# WS2812MATRIX.net
KiCad netlist of a schematic drawn in EAGLE
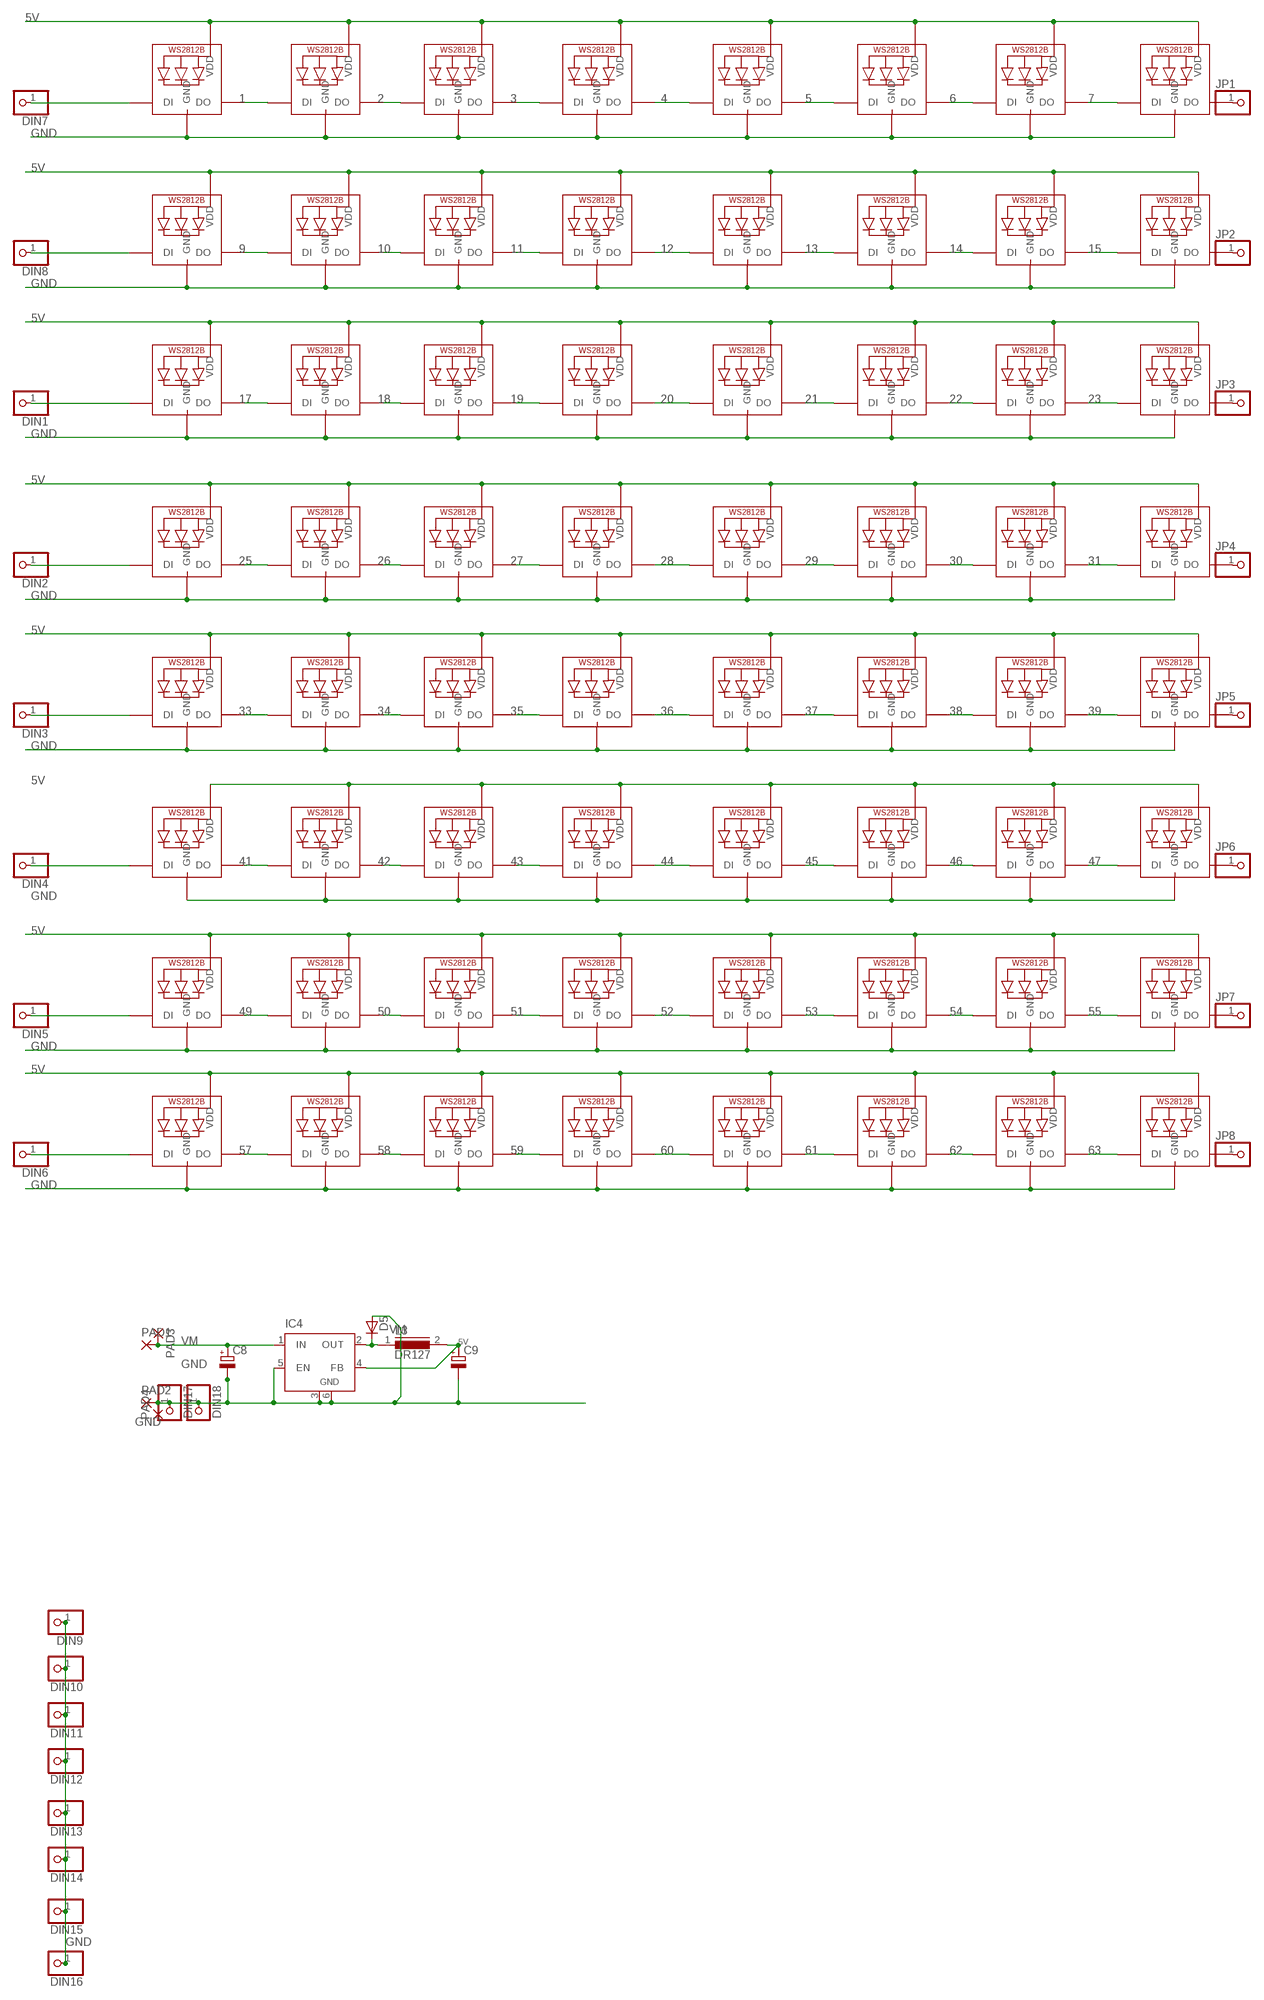
[diagram p0: schematic, sheet 1]

(export (version "E")
  (design (tool "Eeschema 10.0.6"))
  (components
    (comp (ref "C8")
      (value "CPOL-EUE3.5-10")
      (footprint "eagle-import:E3,5-10")
      (libsource (lib "eagle-import") (part "CPOL-EUE3.5-10"))
    )
    (comp (ref "C9")
      (value "CPOL-EUE3.5-10")
      (footprint "eagle-import:E3,5-10")
      (libsource (lib "eagle-import") (part "CPOL-EUE3.5-10"))
    )
    (comp (ref "D5")
      (value "D-SOD-87")
      (footprint "eagle-import:SOD87")
      (libsource (lib "eagle-import") (part "D-SOD-87"))
    )
    (comp (ref "DIN1")
      (value "PINHD-1X1")
      (footprint "eagle-import:1X01")
      (libsource (lib "eagle-import") (part "PINHD-1X1"))
    )
    (comp (ref "DIN2")
      (value "PINHD-1X1")
      (footprint "eagle-import:1X01")
      (libsource (lib "eagle-import") (part "PINHD-1X1"))
    )
    (comp (ref "DIN3")
      (value "PINHD-1X1")
      (footprint "eagle-import:1X01")
      (libsource (lib "eagle-import") (part "PINHD-1X1"))
    )
    (comp (ref "DIN4")
      (value "PINHD-1X1")
      (footprint "eagle-import:1X01")
      (libsource (lib "eagle-import") (part "PINHD-1X1"))
    )
    (comp (ref "DIN5")
      (value "PINHD-1X1")
      (footprint "eagle-import:1X01")
      (libsource (lib "eagle-import") (part "PINHD-1X1"))
    )
    (comp (ref "DIN6")
      (value "PINHD-1X1")
      (footprint "eagle-import:1X01")
      (libsource (lib "eagle-import") (part "PINHD-1X1"))
    )
    (comp (ref "DIN7")
      (value "PINHD-1X1")
      (footprint "eagle-import:1X01")
      (libsource (lib "eagle-import") (part "PINHD-1X1"))
    )
    (comp (ref "DIN8")
      (value "PINHD-1X1")
      (footprint "eagle-import:1X01")
      (libsource (lib "eagle-import") (part "PINHD-1X1"))
    )
    (comp (ref "DIN9")
      (value "PINHD-1X1")
      (footprint "eagle-import:1X01")
      (libsource (lib "eagle-import") (part "PINHD-1X1"))
    )
    (comp (ref "DIN10")
      (value "PINHD-1X1")
      (footprint "eagle-import:1X01")
      (libsource (lib "eagle-import") (part "PINHD-1X1"))
    )
    (comp (ref "DIN11")
      (value "PINHD-1X1")
      (footprint "eagle-import:1X01")
      (libsource (lib "eagle-import") (part "PINHD-1X1"))
    )
    (comp (ref "DIN12")
      (value "PINHD-1X1")
      (footprint "eagle-import:1X01")
      (libsource (lib "eagle-import") (part "PINHD-1X1"))
    )
    (comp (ref "DIN13")
      (value "PINHD-1X1")
      (footprint "eagle-import:1X01")
      (libsource (lib "eagle-import") (part "PINHD-1X1"))
    )
    (comp (ref "DIN14")
      (value "PINHD-1X1")
      (footprint "eagle-import:1X01")
      (libsource (lib "eagle-import") (part "PINHD-1X1"))
    )
    (comp (ref "DIN15")
      (value "PINHD-1X1")
      (footprint "eagle-import:1X01")
      (libsource (lib "eagle-import") (part "PINHD-1X1"))
    )
    (comp (ref "DIN16")
      (value "PINHD-1X1")
      (footprint "eagle-import:1X01")
      (libsource (lib "eagle-import") (part "PINHD-1X1"))
    )
    (comp (ref "DIN17")
      (value "PINHD-1X1")
      (footprint "eagle-import:1X01")
      (libsource (lib "eagle-import") (part "PINHD-1X1"))
    )
    (comp (ref "DIN18")
      (value "PINHD-1X1")
      (footprint "eagle-import:1X01")
      (libsource (lib "eagle-import") (part "PINHD-1X1"))
    )
    (comp (ref "IC4")
      (value "LM2596S")
      (footprint "eagle-import:TO263-5")
      (libsource (lib "eagle-import") (part "LM2596S"))
    )
    (comp (ref "JP1")
      (value "PINHD-1X1")
      (footprint "eagle-import:1X01")
      (libsource (lib "eagle-import") (part "PINHD-1X1"))
    )
    (comp (ref "JP2")
      (value "PINHD-1X1")
      (footprint "eagle-import:1X01")
      (libsource (lib "eagle-import") (part "PINHD-1X1"))
    )
    (comp (ref "JP3")
      (value "PINHD-1X1")
      (footprint "eagle-import:1X01")
      (libsource (lib "eagle-import") (part "PINHD-1X1"))
    )
    (comp (ref "JP4")
      (value "PINHD-1X1")
      (footprint "eagle-import:1X01")
      (libsource (lib "eagle-import") (part "PINHD-1X1"))
    )
    (comp (ref "JP5")
      (value "PINHD-1X1")
      (footprint "eagle-import:1X01")
      (libsource (lib "eagle-import") (part "PINHD-1X1"))
    )
    (comp (ref "JP6")
      (value "PINHD-1X1")
      (footprint "eagle-import:1X01")
      (libsource (lib "eagle-import") (part "PINHD-1X1"))
    )
    (comp (ref "JP7")
      (value "PINHD-1X1")
      (footprint "eagle-import:1X01")
      (libsource (lib "eagle-import") (part "PINHD-1X1"))
    )
    (comp (ref "JP8")
      (value "PINHD-1X1")
      (footprint "eagle-import:1X01")
      (libsource (lib "eagle-import") (part "PINHD-1X1"))
    )
    (comp (ref "L3")
      (value "DR127")
      (footprint "eagle-import:DR127")
      (libsource (lib "eagle-import") (part "DR127"))
    )
    (comp (ref "LED1")
      (value "WS2812B5050")
      (footprint "eagle-import:WS2812B")
      (libsource (lib "eagle-import") (part "WS2812B5050"))
    )
    (comp (ref "LED2")
      (value "WS2812B5050")
      (footprint "eagle-import:WS2812B")
      (libsource (lib "eagle-import") (part "WS2812B5050"))
    )
    (comp (ref "LED3")
      (value "WS2812B5050")
      (footprint "eagle-import:WS2812B")
      (libsource (lib "eagle-import") (part "WS2812B5050"))
    )
    (comp (ref "LED4")
      (value "WS2812B5050")
      (footprint "eagle-import:WS2812B")
      (libsource (lib "eagle-import") (part "WS2812B5050"))
    )
    (comp (ref "LED5")
      (value "WS2812B5050")
      (footprint "eagle-import:WS2812B")
      (libsource (lib "eagle-import") (part "WS2812B5050"))
    )
    (comp (ref "LED6")
      (value "WS2812B5050")
      (footprint "eagle-import:WS2812B")
      (libsource (lib "eagle-import") (part "WS2812B5050"))
    )
    (comp (ref "LED7")
      (value "WS2812B5050")
      (footprint "eagle-import:WS2812B")
      (libsource (lib "eagle-import") (part "WS2812B5050"))
    )
    (comp (ref "LED8")
      (value "WS2812B5050")
      (footprint "eagle-import:WS2812B")
      (libsource (lib "eagle-import") (part "WS2812B5050"))
    )
    (comp (ref "LED9")
      (value "WS2812B5050")
      (footprint "eagle-import:WS2812B")
      (libsource (lib "eagle-import") (part "WS2812B5050"))
    )
    (comp (ref "LED10")
      (value "WS2812B5050")
      (footprint "eagle-import:WS2812B")
      (libsource (lib "eagle-import") (part "WS2812B5050"))
    )
    (comp (ref "LED11")
      (value "WS2812B5050")
      (footprint "eagle-import:WS2812B")
      (libsource (lib "eagle-import") (part "WS2812B5050"))
    )
    (comp (ref "LED12")
      (value "WS2812B5050")
      (footprint "eagle-import:WS2812B")
      (libsource (lib "eagle-import") (part "WS2812B5050"))
    )
    (comp (ref "LED13")
      (value "WS2812B5050")
      (footprint "eagle-import:WS2812B")
      (libsource (lib "eagle-import") (part "WS2812B5050"))
    )
    (comp (ref "LED14")
      (value "WS2812B5050")
      (footprint "eagle-import:WS2812B")
      (libsource (lib "eagle-import") (part "WS2812B5050"))
    )
    (comp (ref "LED15")
      (value "WS2812B5050")
      (footprint "eagle-import:WS2812B")
      (libsource (lib "eagle-import") (part "WS2812B5050"))
    )
    (comp (ref "LED16")
      (value "WS2812B5050")
      (footprint "eagle-import:WS2812B")
      (libsource (lib "eagle-import") (part "WS2812B5050"))
    )
    (comp (ref "LED17")
      (value "WS2812B5050")
      (footprint "eagle-import:WS2812B")
      (libsource (lib "eagle-import") (part "WS2812B5050"))
    )
    (comp (ref "LED18")
      (value "WS2812B5050")
      (footprint "eagle-import:WS2812B")
      (libsource (lib "eagle-import") (part "WS2812B5050"))
    )
    (comp (ref "LED19")
      (value "WS2812B5050")
      (footprint "eagle-import:WS2812B")
      (libsource (lib "eagle-import") (part "WS2812B5050"))
    )
    (comp (ref "LED20")
      (value "WS2812B5050")
      (footprint "eagle-import:WS2812B")
      (libsource (lib "eagle-import") (part "WS2812B5050"))
    )
    (comp (ref "LED21")
      (value "WS2812B5050")
      (footprint "eagle-import:WS2812B")
      (libsource (lib "eagle-import") (part "WS2812B5050"))
    )
    (comp (ref "LED22")
      (value "WS2812B5050")
      (footprint "eagle-import:WS2812B")
      (libsource (lib "eagle-import") (part "WS2812B5050"))
    )
    (comp (ref "LED23")
      (value "WS2812B5050")
      (footprint "eagle-import:WS2812B")
      (libsource (lib "eagle-import") (part "WS2812B5050"))
    )
    (comp (ref "LED24")
      (value "WS2812B5050")
      (footprint "eagle-import:WS2812B")
      (libsource (lib "eagle-import") (part "WS2812B5050"))
    )
    (comp (ref "LED25")
      (value "WS2812B5050")
      (footprint "eagle-import:WS2812B")
      (libsource (lib "eagle-import") (part "WS2812B5050"))
    )
    (comp (ref "LED26")
      (value "WS2812B5050")
      (footprint "eagle-import:WS2812B")
      (libsource (lib "eagle-import") (part "WS2812B5050"))
    )
    (comp (ref "LED27")
      (value "WS2812B5050")
      (footprint "eagle-import:WS2812B")
      (libsource (lib "eagle-import") (part "WS2812B5050"))
    )
    (comp (ref "LED28")
      (value "WS2812B5050")
      (footprint "eagle-import:WS2812B")
      (libsource (lib "eagle-import") (part "WS2812B5050"))
    )
    (comp (ref "LED29")
      (value "WS2812B5050")
      (footprint "eagle-import:WS2812B")
      (libsource (lib "eagle-import") (part "WS2812B5050"))
    )
    (comp (ref "LED30")
      (value "WS2812B5050")
      (footprint "eagle-import:WS2812B")
      (libsource (lib "eagle-import") (part "WS2812B5050"))
    )
    (comp (ref "LED31")
      (value "WS2812B5050")
      (footprint "eagle-import:WS2812B")
      (libsource (lib "eagle-import") (part "WS2812B5050"))
    )
    (comp (ref "LED32")
      (value "WS2812B5050")
      (footprint "eagle-import:WS2812B")
      (libsource (lib "eagle-import") (part "WS2812B5050"))
    )
    (comp (ref "LED33")
      (value "WS2812B5050")
      (footprint "eagle-import:WS2812B")
      (libsource (lib "eagle-import") (part "WS2812B5050"))
    )
    (comp (ref "LED34")
      (value "WS2812B5050")
      (footprint "eagle-import:WS2812B")
      (libsource (lib "eagle-import") (part "WS2812B5050"))
    )
    (comp (ref "LED35")
      (value "WS2812B5050")
      (footprint "eagle-import:WS2812B")
      (libsource (lib "eagle-import") (part "WS2812B5050"))
    )
    (comp (ref "LED36")
      (value "WS2812B5050")
      (footprint "eagle-import:WS2812B")
      (libsource (lib "eagle-import") (part "WS2812B5050"))
    )
    (comp (ref "LED37")
      (value "WS2812B5050")
      (footprint "eagle-import:WS2812B")
      (libsource (lib "eagle-import") (part "WS2812B5050"))
    )
    (comp (ref "LED38")
      (value "WS2812B5050")
      (footprint "eagle-import:WS2812B")
      (libsource (lib "eagle-import") (part "WS2812B5050"))
    )
    (comp (ref "LED39")
      (value "WS2812B5050")
      (footprint "eagle-import:WS2812B")
      (libsource (lib "eagle-import") (part "WS2812B5050"))
    )
    (comp (ref "LED40")
      (value "WS2812B5050")
      (footprint "eagle-import:WS2812B")
      (libsource (lib "eagle-import") (part "WS2812B5050"))
    )
    (comp (ref "LED41")
      (value "WS2812B5050")
      (footprint "eagle-import:WS2812B")
      (libsource (lib "eagle-import") (part "WS2812B5050"))
    )
    (comp (ref "LED42")
      (value "WS2812B5050")
      (footprint "eagle-import:WS2812B")
      (libsource (lib "eagle-import") (part "WS2812B5050"))
    )
    (comp (ref "LED43")
      (value "WS2812B5050")
      (footprint "eagle-import:WS2812B")
      (libsource (lib "eagle-import") (part "WS2812B5050"))
    )
    (comp (ref "LED44")
      (value "WS2812B5050")
      (footprint "eagle-import:WS2812B")
      (libsource (lib "eagle-import") (part "WS2812B5050"))
    )
    (comp (ref "LED45")
      (value "WS2812B5050")
      (footprint "eagle-import:WS2812B")
      (libsource (lib "eagle-import") (part "WS2812B5050"))
    )
    (comp (ref "LED46")
      (value "WS2812B5050")
      (footprint "eagle-import:WS2812B")
      (libsource (lib "eagle-import") (part "WS2812B5050"))
    )
    (comp (ref "LED47")
      (value "WS2812B5050")
      (footprint "eagle-import:WS2812B")
      (libsource (lib "eagle-import") (part "WS2812B5050"))
    )
    (comp (ref "LED48")
      (value "WS2812B5050")
      (footprint "eagle-import:WS2812B")
      (libsource (lib "eagle-import") (part "WS2812B5050"))
    )
    (comp (ref "LED49")
      (value "WS2812B5050")
      (footprint "eagle-import:WS2812B")
      (libsource (lib "eagle-import") (part "WS2812B5050"))
    )
    (comp (ref "LED50")
      (value "WS2812B5050")
      (footprint "eagle-import:WS2812B")
      (libsource (lib "eagle-import") (part "WS2812B5050"))
    )
    (comp (ref "LED51")
      (value "WS2812B5050")
      (footprint "eagle-import:WS2812B")
      (libsource (lib "eagle-import") (part "WS2812B5050"))
    )
    (comp (ref "LED52")
      (value "WS2812B5050")
      (footprint "eagle-import:WS2812B")
      (libsource (lib "eagle-import") (part "WS2812B5050"))
    )
    (comp (ref "LED53")
      (value "WS2812B5050")
      (footprint "eagle-import:WS2812B")
      (libsource (lib "eagle-import") (part "WS2812B5050"))
    )
    (comp (ref "LED54")
      (value "WS2812B5050")
      (footprint "eagle-import:WS2812B")
      (libsource (lib "eagle-import") (part "WS2812B5050"))
    )
    (comp (ref "LED55")
      (value "WS2812B5050")
      (footprint "eagle-import:WS2812B")
      (libsource (lib "eagle-import") (part "WS2812B5050"))
    )
    (comp (ref "LED56")
      (value "WS2812B5050")
      (footprint "eagle-import:WS2812B")
      (libsource (lib "eagle-import") (part "WS2812B5050"))
    )
    (comp (ref "LED57")
      (value "WS2812B5050")
      (footprint "eagle-import:WS2812B")
      (libsource (lib "eagle-import") (part "WS2812B5050"))
    )
    (comp (ref "LED58")
      (value "WS2812B5050")
      (footprint "eagle-import:WS2812B")
      (libsource (lib "eagle-import") (part "WS2812B5050"))
    )
    (comp (ref "LED59")
      (value "WS2812B5050")
      (footprint "eagle-import:WS2812B")
      (libsource (lib "eagle-import") (part "WS2812B5050"))
    )
    (comp (ref "LED60")
      (value "WS2812B5050")
      (footprint "eagle-import:WS2812B")
      (libsource (lib "eagle-import") (part "WS2812B5050"))
    )
    (comp (ref "LED61")
      (value "WS2812B5050")
      (footprint "eagle-import:WS2812B")
      (libsource (lib "eagle-import") (part "WS2812B5050"))
    )
    (comp (ref "LED62")
      (value "WS2812B5050")
      (footprint "eagle-import:WS2812B")
      (libsource (lib "eagle-import") (part "WS2812B5050"))
    )
    (comp (ref "LED63")
      (value "WS2812B5050")
      (footprint "eagle-import:WS2812B")
      (libsource (lib "eagle-import") (part "WS2812B5050"))
    )
    (comp (ref "LED64")
      (value "WS2812B5050")
      (footprint "eagle-import:WS2812B")
      (libsource (lib "eagle-import") (part "WS2812B5050"))
    )
    (comp (ref "PAD1")
      (value "2,54/1,1")
      (footprint "eagle-import:2,54_1,1")
      (libsource (lib "eagle-import") (part "2,54/1,1"))
    )
    (comp (ref "PAD2")
      (value "2,54/1,1")
      (footprint "eagle-import:2,54_1,1")
      (libsource (lib "eagle-import") (part "2,54/1,1"))
    )
    (comp (ref "PAD3")
      (value "2,54/1,1")
      (footprint "eagle-import:2,54_1,1")
      (libsource (lib "eagle-import") (part "2,54/1,1"))
    )
    (comp (ref "PAD4")
      (value "2,54/1,1")
      (footprint "eagle-import:2,54_1,1")
      (libsource (lib "eagle-import") (part "2,54/1,1"))
    )
  )
  (nets
    (net (code "1") (name "/1") (class "Default")
      (node (ref "LED10") (pin "4-DIN") (pinfunction "DI_4-DIN") (pintype "input"))
      (node (ref "LED9") (pin "2-DOUT") (pinfunction "DO_2-DOUT") (pintype "output"))
    )
    (net (code "2") (name "/2") (class "Default")
      (node (ref "LED10") (pin "2-DOUT") (pinfunction "DO_2-DOUT") (pintype "output"))
      (node (ref "LED11") (pin "4-DIN") (pinfunction "DI_4-DIN") (pintype "input"))
    )
    (net (code "3") (name "/3") (class "Default")
      (node (ref "LED11") (pin "2-DOUT") (pinfunction "DO_2-DOUT") (pintype "output"))
      (node (ref "LED12") (pin "4-DIN") (pinfunction "DI_4-DIN") (pintype "input"))
    )
    (net (code "4") (name "/4") (class "Default")
      (node (ref "LED12") (pin "2-DOUT") (pinfunction "DO_2-DOUT") (pintype "output"))
      (node (ref "LED13") (pin "4-DIN") (pinfunction "DI_4-DIN") (pintype "input"))
    )
    (net (code "5") (name "/5") (class "Default")
      (node (ref "LED13") (pin "2-DOUT") (pinfunction "DO_2-DOUT") (pintype "output"))
      (node (ref "LED14") (pin "4-DIN") (pinfunction "DI_4-DIN") (pintype "input"))
    )
    (net (code "6") (name "/5V") (class "Default")
      (node (ref "C9") (pin "+") (pinfunction "+_+") (pintype "passive"))
      (node (ref "IC4") (pin "4") (pinfunction "FB_4") (pintype "input"))
      (node (ref "L3") (pin "2") (pinfunction "2_2") (pintype "passive"))
      (node (ref "LED1") (pin "1-VDD") (pinfunction "VDD_1-VDD") (pintype "power_in"))
      (node (ref "LED10") (pin "1-VDD") (pinfunction "VDD_1-VDD") (pintype "power_in"))
      (node (ref "LED11") (pin "1-VDD") (pinfunction "VDD_1-VDD") (pintype "power_in"))
      (node (ref "LED12") (pin "1-VDD") (pinfunction "VDD_1-VDD") (pintype "power_in"))
      (node (ref "LED13") (pin "1-VDD") (pinfunction "VDD_1-VDD") (pintype "power_in"))
      (node (ref "LED14") (pin "1-VDD") (pinfunction "VDD_1-VDD") (pintype "power_in"))
      (node (ref "LED15") (pin "1-VDD") (pinfunction "VDD_1-VDD") (pintype "power_in"))
      (node (ref "LED16") (pin "1-VDD") (pinfunction "VDD_1-VDD") (pintype "power_in"))
      (node (ref "LED17") (pin "1-VDD") (pinfunction "VDD_1-VDD") (pintype "power_in"))
      (node (ref "LED18") (pin "1-VDD") (pinfunction "VDD_1-VDD") (pintype "power_in"))
      (node (ref "LED19") (pin "1-VDD") (pinfunction "VDD_1-VDD") (pintype "power_in"))
      (node (ref "LED2") (pin "1-VDD") (pinfunction "VDD_1-VDD") (pintype "power_in"))
      (node (ref "LED20") (pin "1-VDD") (pinfunction "VDD_1-VDD") (pintype "power_in"))
      (node (ref "LED21") (pin "1-VDD") (pinfunction "VDD_1-VDD") (pintype "power_in"))
      (node (ref "LED22") (pin "1-VDD") (pinfunction "VDD_1-VDD") (pintype "power_in"))
      (node (ref "LED23") (pin "1-VDD") (pinfunction "VDD_1-VDD") (pintype "power_in"))
      (node (ref "LED24") (pin "1-VDD") (pinfunction "VDD_1-VDD") (pintype "power_in"))
      (node (ref "LED25") (pin "1-VDD") (pinfunction "VDD_1-VDD") (pintype "power_in"))
      (node (ref "LED26") (pin "1-VDD") (pinfunction "VDD_1-VDD") (pintype "power_in"))
      (node (ref "LED27") (pin "1-VDD") (pinfunction "VDD_1-VDD") (pintype "power_in"))
      (node (ref "LED28") (pin "1-VDD") (pinfunction "VDD_1-VDD") (pintype "power_in"))
      (node (ref "LED29") (pin "1-VDD") (pinfunction "VDD_1-VDD") (pintype "power_in"))
      (node (ref "LED3") (pin "1-VDD") (pinfunction "VDD_1-VDD") (pintype "power_in"))
      (node (ref "LED30") (pin "1-VDD") (pinfunction "VDD_1-VDD") (pintype "power_in"))
      (node (ref "LED31") (pin "1-VDD") (pinfunction "VDD_1-VDD") (pintype "power_in"))
      (node (ref "LED32") (pin "1-VDD") (pinfunction "VDD_1-VDD") (pintype "power_in"))
      (node (ref "LED33") (pin "1-VDD") (pinfunction "VDD_1-VDD") (pintype "power_in"))
      (node (ref "LED34") (pin "1-VDD") (pinfunction "VDD_1-VDD") (pintype "power_in"))
      (node (ref "LED35") (pin "1-VDD") (pinfunction "VDD_1-VDD") (pintype "power_in"))
      (node (ref "LED36") (pin "1-VDD") (pinfunction "VDD_1-VDD") (pintype "power_in"))
      (node (ref "LED37") (pin "1-VDD") (pinfunction "VDD_1-VDD") (pintype "power_in"))
      (node (ref "LED38") (pin "1-VDD") (pinfunction "VDD_1-VDD") (pintype "power_in"))
      (node (ref "LED39") (pin "1-VDD") (pinfunction "VDD_1-VDD") (pintype "power_in"))
      (node (ref "LED4") (pin "1-VDD") (pinfunction "VDD_1-VDD") (pintype "power_in"))
      (node (ref "LED40") (pin "1-VDD") (pinfunction "VDD_1-VDD") (pintype "power_in"))
      (node (ref "LED41") (pin "1-VDD") (pinfunction "VDD_1-VDD") (pintype "power_in"))
      (node (ref "LED42") (pin "1-VDD") (pinfunction "VDD_1-VDD") (pintype "power_in"))
      (node (ref "LED43") (pin "1-VDD") (pinfunction "VDD_1-VDD") (pintype "power_in"))
      (node (ref "LED44") (pin "1-VDD") (pinfunction "VDD_1-VDD") (pintype "power_in"))
      (node (ref "LED45") (pin "1-VDD") (pinfunction "VDD_1-VDD") (pintype "power_in"))
      (node (ref "LED46") (pin "1-VDD") (pinfunction "VDD_1-VDD") (pintype "power_in"))
      (node (ref "LED47") (pin "1-VDD") (pinfunction "VDD_1-VDD") (pintype "power_in"))
      (node (ref "LED48") (pin "1-VDD") (pinfunction "VDD_1-VDD") (pintype "power_in"))
      (node (ref "LED49") (pin "1-VDD") (pinfunction "VDD_1-VDD") (pintype "power_in"))
      (node (ref "LED5") (pin "1-VDD") (pinfunction "VDD_1-VDD") (pintype "power_in"))
      (node (ref "LED50") (pin "1-VDD") (pinfunction "VDD_1-VDD") (pintype "power_in"))
      (node (ref "LED51") (pin "1-VDD") (pinfunction "VDD_1-VDD") (pintype "power_in"))
      (node (ref "LED52") (pin "1-VDD") (pinfunction "VDD_1-VDD") (pintype "power_in"))
      (node (ref "LED53") (pin "1-VDD") (pinfunction "VDD_1-VDD") (pintype "power_in"))
      (node (ref "LED54") (pin "1-VDD") (pinfunction "VDD_1-VDD") (pintype "power_in"))
      (node (ref "LED55") (pin "1-VDD") (pinfunction "VDD_1-VDD") (pintype "power_in"))
      (node (ref "LED56") (pin "1-VDD") (pinfunction "VDD_1-VDD") (pintype "power_in"))
      (node (ref "LED57") (pin "1-VDD") (pinfunction "VDD_1-VDD") (pintype "power_in"))
      (node (ref "LED58") (pin "1-VDD") (pinfunction "VDD_1-VDD") (pintype "power_in"))
      (node (ref "LED59") (pin "1-VDD") (pinfunction "VDD_1-VDD") (pintype "power_in"))
      (node (ref "LED6") (pin "1-VDD") (pinfunction "VDD_1-VDD") (pintype "power_in"))
      (node (ref "LED60") (pin "1-VDD") (pinfunction "VDD_1-VDD") (pintype "power_in"))
      (node (ref "LED61") (pin "1-VDD") (pinfunction "VDD_1-VDD") (pintype "power_in"))
      (node (ref "LED62") (pin "1-VDD") (pinfunction "VDD_1-VDD") (pintype "power_in"))
      (node (ref "LED63") (pin "1-VDD") (pinfunction "VDD_1-VDD") (pintype "power_in"))
      (node (ref "LED64") (pin "1-VDD") (pinfunction "VDD_1-VDD") (pintype "power_in"))
      (node (ref "LED7") (pin "1-VDD") (pinfunction "VDD_1-VDD") (pintype "power_in"))
      (node (ref "LED8") (pin "1-VDD") (pinfunction "VDD_1-VDD") (pintype "power_in"))
      (node (ref "LED9") (pin "1-VDD") (pinfunction "VDD_1-VDD") (pintype "power_in"))
    )
    (net (code "7") (name "/6") (class "Default")
      (node (ref "LED14") (pin "2-DOUT") (pinfunction "DO_2-DOUT") (pintype "output"))
      (node (ref "LED15") (pin "4-DIN") (pinfunction "DI_4-DIN") (pintype "input"))
    )
    (net (code "8") (name "/7") (class "Default")
      (node (ref "LED15") (pin "2-DOUT") (pinfunction "DO_2-DOUT") (pintype "output"))
      (node (ref "LED16") (pin "4-DIN") (pinfunction "DI_4-DIN") (pintype "input"))
    )
    (net (code "9") (name "/9") (class "Default")
      (node (ref "LED1") (pin "2-DOUT") (pinfunction "DO_2-DOUT") (pintype "output"))
      (node (ref "LED2") (pin "4-DIN") (pinfunction "DI_4-DIN") (pintype "input"))
    )
    (net (code "10") (name "/10") (class "Default")
      (node (ref "LED2") (pin "2-DOUT") (pinfunction "DO_2-DOUT") (pintype "output"))
      (node (ref "LED3") (pin "4-DIN") (pinfunction "DI_4-DIN") (pintype "input"))
    )
    (net (code "11") (name "/11") (class "Default")
      (node (ref "LED3") (pin "2-DOUT") (pinfunction "DO_2-DOUT") (pintype "output"))
      (node (ref "LED4") (pin "4-DIN") (pinfunction "DI_4-DIN") (pintype "input"))
    )
    (net (code "12") (name "/12") (class "Default")
      (node (ref "LED4") (pin "2-DOUT") (pinfunction "DO_2-DOUT") (pintype "output"))
      (node (ref "LED5") (pin "4-DIN") (pinfunction "DI_4-DIN") (pintype "input"))
    )
    (net (code "13") (name "/13") (class "Default")
      (node (ref "LED5") (pin "2-DOUT") (pinfunction "DO_2-DOUT") (pintype "output"))
      (node (ref "LED6") (pin "4-DIN") (pinfunction "DI_4-DIN") (pintype "input"))
    )
    (net (code "14") (name "/14") (class "Default")
      (node (ref "LED6") (pin "2-DOUT") (pinfunction "DO_2-DOUT") (pintype "output"))
      (node (ref "LED7") (pin "4-DIN") (pinfunction "DI_4-DIN") (pintype "input"))
    )
    (net (code "15") (name "/15") (class "Default")
      (node (ref "LED7") (pin "2-DOUT") (pinfunction "DO_2-DOUT") (pintype "output"))
      (node (ref "LED8") (pin "4-DIN") (pinfunction "DI_4-DIN") (pintype "input"))
    )
    (net (code "16") (name "/17") (class "Default")
      (node (ref "LED17") (pin "2-DOUT") (pinfunction "DO_2-DOUT") (pintype "output"))
      (node (ref "LED18") (pin "4-DIN") (pinfunction "DI_4-DIN") (pintype "input"))
    )
    (net (code "17") (name "/18") (class "Default")
      (node (ref "LED18") (pin "2-DOUT") (pinfunction "DO_2-DOUT") (pintype "output"))
      (node (ref "LED19") (pin "4-DIN") (pinfunction "DI_4-DIN") (pintype "input"))
    )
    (net (code "18") (name "/19") (class "Default")
      (node (ref "LED19") (pin "2-DOUT") (pinfunction "DO_2-DOUT") (pintype "output"))
      (node (ref "LED20") (pin "4-DIN") (pinfunction "DI_4-DIN") (pintype "input"))
    )
    (net (code "19") (name "/20") (class "Default")
      (node (ref "LED20") (pin "2-DOUT") (pinfunction "DO_2-DOUT") (pintype "output"))
      (node (ref "LED21") (pin "4-DIN") (pinfunction "DI_4-DIN") (pintype "input"))
    )
    (net (code "20") (name "/21") (class "Default")
      (node (ref "LED21") (pin "2-DOUT") (pinfunction "DO_2-DOUT") (pintype "output"))
      (node (ref "LED22") (pin "4-DIN") (pinfunction "DI_4-DIN") (pintype "input"))
    )
    (net (code "21") (name "/22") (class "Default")
      (node (ref "LED22") (pin "2-DOUT") (pinfunction "DO_2-DOUT") (pintype "output"))
      (node (ref "LED23") (pin "4-DIN") (pinfunction "DI_4-DIN") (pintype "input"))
    )
    (net (code "22") (name "/23") (class "Default")
      (node (ref "LED23") (pin "2-DOUT") (pinfunction "DO_2-DOUT") (pintype "output"))
      (node (ref "LED24") (pin "4-DIN") (pinfunction "DI_4-DIN") (pintype "input"))
    )
    (net (code "23") (name "/25") (class "Default")
      (node (ref "LED25") (pin "2-DOUT") (pinfunction "DO_2-DOUT") (pintype "output"))
      (node (ref "LED26") (pin "4-DIN") (pinfunction "DI_4-DIN") (pintype "input"))
    )
    (net (code "24") (name "/26") (class "Default")
      (node (ref "LED26") (pin "2-DOUT") (pinfunction "DO_2-DOUT") (pintype "output"))
      (node (ref "LED27") (pin "4-DIN") (pinfunction "DI_4-DIN") (pintype "input"))
    )
    (net (code "25") (name "/27") (class "Default")
      (node (ref "LED27") (pin "2-DOUT") (pinfunction "DO_2-DOUT") (pintype "output"))
      (node (ref "LED28") (pin "4-DIN") (pinfunction "DI_4-DIN") (pintype "input"))
    )
    (net (code "26") (name "/28") (class "Default")
      (node (ref "LED28") (pin "2-DOUT") (pinfunction "DO_2-DOUT") (pintype "output"))
      (node (ref "LED29") (pin "4-DIN") (pinfunction "DI_4-DIN") (pintype "input"))
    )
    (net (code "27") (name "/29") (class "Default")
      (node (ref "LED29") (pin "2-DOUT") (pinfunction "DO_2-DOUT") (pintype "output"))
      (node (ref "LED30") (pin "4-DIN") (pinfunction "DI_4-DIN") (pintype "input"))
    )
    (net (code "28") (name "/30") (class "Default")
      (node (ref "LED30") (pin "2-DOUT") (pinfunction "DO_2-DOUT") (pintype "output"))
      (node (ref "LED31") (pin "4-DIN") (pinfunction "DI_4-DIN") (pintype "input"))
    )
    (net (code "29") (name "/31") (class "Default")
      (node (ref "LED31") (pin "2-DOUT") (pinfunction "DO_2-DOUT") (pintype "output"))
      (node (ref "LED32") (pin "4-DIN") (pinfunction "DI_4-DIN") (pintype "input"))
    )
    (net (code "30") (name "/33") (class "Default")
      (node (ref "LED33") (pin "2-DOUT") (pinfunction "DO_2-DOUT") (pintype "output"))
      (node (ref "LED34") (pin "4-DIN") (pinfunction "DI_4-DIN") (pintype "input"))
    )
    (net (code "31") (name "/34") (class "Default")
      (node (ref "LED34") (pin "2-DOUT") (pinfunction "DO_2-DOUT") (pintype "output"))
      (node (ref "LED35") (pin "4-DIN") (pinfunction "DI_4-DIN") (pintype "input"))
    )
    (net (code "32") (name "/35") (class "Default")
      (node (ref "LED35") (pin "2-DOUT") (pinfunction "DO_2-DOUT") (pintype "output"))
      (node (ref "LED36") (pin "4-DIN") (pinfunction "DI_4-DIN") (pintype "input"))
    )
    (net (code "33") (name "/36") (class "Default")
      (node (ref "LED36") (pin "2-DOUT") (pinfunction "DO_2-DOUT") (pintype "output"))
      (node (ref "LED37") (pin "4-DIN") (pinfunction "DI_4-DIN") (pintype "input"))
    )
    (net (code "34") (name "/37") (class "Default")
      (node (ref "LED37") (pin "2-DOUT") (pinfunction "DO_2-DOUT") (pintype "output"))
      (node (ref "LED38") (pin "4-DIN") (pinfunction "DI_4-DIN") (pintype "input"))
    )
    (net (code "35") (name "/38") (class "Default")
      (node (ref "LED38") (pin "2-DOUT") (pinfunction "DO_2-DOUT") (pintype "output"))
      (node (ref "LED39") (pin "4-DIN") (pinfunction "DI_4-DIN") (pintype "input"))
    )
    (net (code "36") (name "/39") (class "Default")
      (node (ref "LED39") (pin "2-DOUT") (pinfunction "DO_2-DOUT") (pintype "output"))
      (node (ref "LED40") (pin "4-DIN") (pinfunction "DI_4-DIN") (pintype "input"))
    )
    (net (code "37") (name "/41") (class "Default")
      (node (ref "LED41") (pin "2-DOUT") (pinfunction "DO_2-DOUT") (pintype "output"))
      (node (ref "LED42") (pin "4-DIN") (pinfunction "DI_4-DIN") (pintype "input"))
    )
    (net (code "38") (name "/42") (class "Default")
      (node (ref "LED42") (pin "2-DOUT") (pinfunction "DO_2-DOUT") (pintype "output"))
      (node (ref "LED43") (pin "4-DIN") (pinfunction "DI_4-DIN") (pintype "input"))
    )
    (net (code "39") (name "/43") (class "Default")
      (node (ref "LED43") (pin "2-DOUT") (pinfunction "DO_2-DOUT") (pintype "output"))
      (node (ref "LED44") (pin "4-DIN") (pinfunction "DI_4-DIN") (pintype "input"))
    )
    (net (code "40") (name "/44") (class "Default")
      (node (ref "LED44") (pin "2-DOUT") (pinfunction "DO_2-DOUT") (pintype "output"))
      (node (ref "LED45") (pin "4-DIN") (pinfunction "DI_4-DIN") (pintype "input"))
    )
    (net (code "41") (name "/45") (class "Default")
      (node (ref "LED45") (pin "2-DOUT") (pinfunction "DO_2-DOUT") (pintype "output"))
      (node (ref "LED46") (pin "4-DIN") (pinfunction "DI_4-DIN") (pintype "input"))
    )
    (net (code "42") (name "/46") (class "Default")
      (node (ref "LED46") (pin "2-DOUT") (pinfunction "DO_2-DOUT") (pintype "output"))
      (node (ref "LED47") (pin "4-DIN") (pinfunction "DI_4-DIN") (pintype "input"))
    )
    (net (code "43") (name "/47") (class "Default")
      (node (ref "LED47") (pin "2-DOUT") (pinfunction "DO_2-DOUT") (pintype "output"))
      (node (ref "LED48") (pin "4-DIN") (pinfunction "DI_4-DIN") (pintype "input"))
    )
    (net (code "44") (name "/49") (class "Default")
      (node (ref "LED49") (pin "2-DOUT") (pinfunction "DO_2-DOUT") (pintype "output"))
      (node (ref "LED50") (pin "4-DIN") (pinfunction "DI_4-DIN") (pintype "input"))
    )
    (net (code "45") (name "/50") (class "Default")
      (node (ref "LED50") (pin "2-DOUT") (pinfunction "DO_2-DOUT") (pintype "output"))
      (node (ref "LED51") (pin "4-DIN") (pinfunction "DI_4-DIN") (pintype "input"))
    )
    (net (code "46") (name "/51") (class "Default")
      (node (ref "LED51") (pin "2-DOUT") (pinfunction "DO_2-DOUT") (pintype "output"))
      (node (ref "LED52") (pin "4-DIN") (pinfunction "DI_4-DIN") (pintype "input"))
    )
    (net (code "47") (name "/52") (class "Default")
      (node (ref "LED52") (pin "2-DOUT") (pinfunction "DO_2-DOUT") (pintype "output"))
      (node (ref "LED53") (pin "4-DIN") (pinfunction "DI_4-DIN") (pintype "input"))
    )
    (net (code "48") (name "/53") (class "Default")
      (node (ref "LED53") (pin "2-DOUT") (pinfunction "DO_2-DOUT") (pintype "output"))
      (node (ref "LED54") (pin "4-DIN") (pinfunction "DI_4-DIN") (pintype "input"))
    )
    (net (code "49") (name "/54") (class "Default")
      (node (ref "LED54") (pin "2-DOUT") (pinfunction "DO_2-DOUT") (pintype "output"))
      (node (ref "LED55") (pin "4-DIN") (pinfunction "DI_4-DIN") (pintype "input"))
    )
    (net (code "50") (name "/55") (class "Default")
      (node (ref "LED55") (pin "2-DOUT") (pinfunction "DO_2-DOUT") (pintype "output"))
      (node (ref "LED56") (pin "4-DIN") (pinfunction "DI_4-DIN") (pintype "input"))
    )
    (net (code "51") (name "/57") (class "Default")
      (node (ref "LED57") (pin "2-DOUT") (pinfunction "DO_2-DOUT") (pintype "output"))
      (node (ref "LED58") (pin "4-DIN") (pinfunction "DI_4-DIN") (pintype "input"))
    )
    (net (code "52") (name "/58") (class "Default")
      (node (ref "LED58") (pin "2-DOUT") (pinfunction "DO_2-DOUT") (pintype "output"))
      (node (ref "LED59") (pin "4-DIN") (pinfunction "DI_4-DIN") (pintype "input"))
    )
    (net (code "53") (name "/59") (class "Default")
      (node (ref "LED59") (pin "2-DOUT") (pinfunction "DO_2-DOUT") (pintype "output"))
      (node (ref "LED60") (pin "4-DIN") (pinfunction "DI_4-DIN") (pintype "input"))
    )
    (net (code "54") (name "/60") (class "Default")
      (node (ref "LED60") (pin "2-DOUT") (pinfunction "DO_2-DOUT") (pintype "output"))
      (node (ref "LED61") (pin "4-DIN") (pinfunction "DI_4-DIN") (pintype "input"))
    )
    (net (code "55") (name "/61") (class "Default")
      (node (ref "LED61") (pin "2-DOUT") (pinfunction "DO_2-DOUT") (pintype "output"))
      (node (ref "LED62") (pin "4-DIN") (pinfunction "DI_4-DIN") (pintype "input"))
    )
    (net (code "56") (name "/62") (class "Default")
      (node (ref "LED62") (pin "2-DOUT") (pinfunction "DO_2-DOUT") (pintype "output"))
      (node (ref "LED63") (pin "4-DIN") (pinfunction "DI_4-DIN") (pintype "input"))
    )
    (net (code "57") (name "/63") (class "Default")
      (node (ref "LED63") (pin "2-DOUT") (pinfunction "DO_2-DOUT") (pintype "output"))
      (node (ref "LED64") (pin "4-DIN") (pinfunction "DI_4-DIN") (pintype "input"))
    )
    (net (code "58") (name "/GND") (class "Default")
      (node (ref "C8") (pin "-") (pinfunction "-_-") (pintype "passive"))
      (node (ref "C9") (pin "-") (pinfunction "-_-") (pintype "passive"))
      (node (ref "D5") (pin "2") (pinfunction "A_2") (pintype "passive"))
      (node (ref "DIN10") (pin "1") (pinfunction "1_1") (pintype "passive"))
      (node (ref "DIN11") (pin "1") (pinfunction "1_1") (pintype "passive"))
      (node (ref "DIN12") (pin "1") (pinfunction "1_1") (pintype "passive"))
      (node (ref "DIN13") (pin "1") (pinfunction "1_1") (pintype "passive"))
      (node (ref "DIN14") (pin "1") (pinfunction "1_1") (pintype "passive"))
      (node (ref "DIN15") (pin "1") (pinfunction "1_1") (pintype "passive"))
      (node (ref "DIN16") (pin "1") (pinfunction "1_1") (pintype "passive"))
      (node (ref "DIN17") (pin "1") (pinfunction "1_1") (pintype "passive"))
      (node (ref "DIN18") (pin "1") (pinfunction "1_1") (pintype "passive"))
      (node (ref "DIN9") (pin "1") (pinfunction "1_1") (pintype "passive"))
      (node (ref "IC4") (pin "3") (pinfunction "GND_3") (pintype "power_in"))
      (node (ref "IC4") (pin "5") (pinfunction "EN_5") (pintype "input"))
      (node (ref "IC4") (pin "6") (pinfunction "GND_6") (pintype "power_in"))
      (node (ref "LED1") (pin "3-GND") (pinfunction "GND_3-GND") (pintype "power_in"))
      (node (ref "LED10") (pin "3-GND") (pinfunction "GND_3-GND") (pintype "power_in"))
      (node (ref "LED11") (pin "3-GND") (pinfunction "GND_3-GND") (pintype "power_in"))
      (node (ref "LED12") (pin "3-GND") (pinfunction "GND_3-GND") (pintype "power_in"))
      (node (ref "LED13") (pin "3-GND") (pinfunction "GND_3-GND") (pintype "power_in"))
      (node (ref "LED14") (pin "3-GND") (pinfunction "GND_3-GND") (pintype "power_in"))
      (node (ref "LED15") (pin "3-GND") (pinfunction "GND_3-GND") (pintype "power_in"))
      (node (ref "LED16") (pin "3-GND") (pinfunction "GND_3-GND") (pintype "power_in"))
      (node (ref "LED17") (pin "3-GND") (pinfunction "GND_3-GND") (pintype "power_in"))
      (node (ref "LED18") (pin "3-GND") (pinfunction "GND_3-GND") (pintype "power_in"))
      (node (ref "LED19") (pin "3-GND") (pinfunction "GND_3-GND") (pintype "power_in"))
      (node (ref "LED2") (pin "3-GND") (pinfunction "GND_3-GND") (pintype "power_in"))
      (node (ref "LED20") (pin "3-GND") (pinfunction "GND_3-GND") (pintype "power_in"))
      (node (ref "LED21") (pin "3-GND") (pinfunction "GND_3-GND") (pintype "power_in"))
      (node (ref "LED22") (pin "3-GND") (pinfunction "GND_3-GND") (pintype "power_in"))
      (node (ref "LED23") (pin "3-GND") (pinfunction "GND_3-GND") (pintype "power_in"))
      (node (ref "LED24") (pin "3-GND") (pinfunction "GND_3-GND") (pintype "power_in"))
      (node (ref "LED25") (pin "3-GND") (pinfunction "GND_3-GND") (pintype "power_in"))
      (node (ref "LED26") (pin "3-GND") (pinfunction "GND_3-GND") (pintype "power_in"))
      (node (ref "LED27") (pin "3-GND") (pinfunction "GND_3-GND") (pintype "power_in"))
      (node (ref "LED28") (pin "3-GND") (pinfunction "GND_3-GND") (pintype "power_in"))
      (node (ref "LED29") (pin "3-GND") (pinfunction "GND_3-GND") (pintype "power_in"))
      (node (ref "LED3") (pin "3-GND") (pinfunction "GND_3-GND") (pintype "power_in"))
      (node (ref "LED30") (pin "3-GND") (pinfunction "GND_3-GND") (pintype "power_in"))
      (node (ref "LED31") (pin "3-GND") (pinfunction "GND_3-GND") (pintype "power_in"))
      (node (ref "LED32") (pin "3-GND") (pinfunction "GND_3-GND") (pintype "power_in"))
      (node (ref "LED33") (pin "3-GND") (pinfunction "GND_3-GND") (pintype "power_in"))
      (node (ref "LED34") (pin "3-GND") (pinfunction "GND_3-GND") (pintype "power_in"))
      (node (ref "LED35") (pin "3-GND") (pinfunction "GND_3-GND") (pintype "power_in"))
      (node (ref "LED36") (pin "3-GND") (pinfunction "GND_3-GND") (pintype "power_in"))
      (node (ref "LED37") (pin "3-GND") (pinfunction "GND_3-GND") (pintype "power_in"))
      (node (ref "LED38") (pin "3-GND") (pinfunction "GND_3-GND") (pintype "power_in"))
      (node (ref "LED39") (pin "3-GND") (pinfunction "GND_3-GND") (pintype "power_in"))
      (node (ref "LED4") (pin "3-GND") (pinfunction "GND_3-GND") (pintype "power_in"))
      (node (ref "LED40") (pin "3-GND") (pinfunction "GND_3-GND") (pintype "power_in"))
      (node (ref "LED41") (pin "3-GND") (pinfunction "GND_3-GND") (pintype "power_in"))
      (node (ref "LED42") (pin "3-GND") (pinfunction "GND_3-GND") (pintype "power_in"))
      (node (ref "LED43") (pin "3-GND") (pinfunction "GND_3-GND") (pintype "power_in"))
      (node (ref "LED44") (pin "3-GND") (pinfunction "GND_3-GND") (pintype "power_in"))
      (node (ref "LED45") (pin "3-GND") (pinfunction "GND_3-GND") (pintype "power_in"))
      (node (ref "LED46") (pin "3-GND") (pinfunction "GND_3-GND") (pintype "power_in"))
      (node (ref "LED47") (pin "3-GND") (pinfunction "GND_3-GND") (pintype "power_in"))
      (node (ref "LED48") (pin "3-GND") (pinfunction "GND_3-GND") (pintype "power_in"))
      (node (ref "LED49") (pin "3-GND") (pinfunction "GND_3-GND") (pintype "power_in"))
      (node (ref "LED5") (pin "3-GND") (pinfunction "GND_3-GND") (pintype "power_in"))
      (node (ref "LED50") (pin "3-GND") (pinfunction "GND_3-GND") (pintype "power_in"))
      (node (ref "LED51") (pin "3-GND") (pinfunction "GND_3-GND") (pintype "power_in"))
      (node (ref "LED52") (pin "3-GND") (pinfunction "GND_3-GND") (pintype "power_in"))
      (node (ref "LED53") (pin "3-GND") (pinfunction "GND_3-GND") (pintype "power_in"))
      (node (ref "LED54") (pin "3-GND") (pinfunction "GND_3-GND") (pintype "power_in"))
      (node (ref "LED55") (pin "3-GND") (pinfunction "GND_3-GND") (pintype "power_in"))
      (node (ref "LED56") (pin "3-GND") (pinfunction "GND_3-GND") (pintype "power_in"))
      (node (ref "LED57") (pin "3-GND") (pinfunction "GND_3-GND") (pintype "power_in"))
      (node (ref "LED58") (pin "3-GND") (pinfunction "GND_3-GND") (pintype "power_in"))
      (node (ref "LED59") (pin "3-GND") (pinfunction "GND_3-GND") (pintype "power_in"))
      (node (ref "LED6") (pin "3-GND") (pinfunction "GND_3-GND") (pintype "power_in"))
      (node (ref "LED60") (pin "3-GND") (pinfunction "GND_3-GND") (pintype "power_in"))
      (node (ref "LED61") (pin "3-GND") (pinfunction "GND_3-GND") (pintype "power_in"))
      (node (ref "LED62") (pin "3-GND") (pinfunction "GND_3-GND") (pintype "power_in"))
      (node (ref "LED63") (pin "3-GND") (pinfunction "GND_3-GND") (pintype "power_in"))
      (node (ref "LED64") (pin "3-GND") (pinfunction "GND_3-GND") (pintype "power_in"))
      (node (ref "LED7") (pin "3-GND") (pinfunction "GND_3-GND") (pintype "power_in"))
      (node (ref "LED8") (pin "3-GND") (pinfunction "GND_3-GND") (pintype "power_in"))
      (node (ref "LED9") (pin "3-GND") (pinfunction "GND_3-GND") (pintype "power_in"))
      (node (ref "PAD2") (pin "1") (pinfunction "P_1") (pintype "passive"))
      (node (ref "PAD4") (pin "1") (pinfunction "P_1") (pintype "passive"))
    )
    (net (code "59") (name "/VM") (class "Default")
      (node (ref "C8") (pin "+") (pinfunction "+_+") (pintype "passive"))
      (node (ref "IC4") (pin "1") (pinfunction "IN_1") (pintype "input"))
      (node (ref "PAD1") (pin "1") (pinfunction "P_1") (pintype "passive"))
      (node (ref "PAD3") (pin "1") (pinfunction "P_1") (pintype "passive"))
    )
    (net (code "60") (name "Net-(D5-C)") (class "Default")
      (node (ref "D5") (pin "1") (pinfunction "C_1") (pintype "passive"))
      (node (ref "IC4") (pin "2") (pinfunction "OUT_2") (pintype "output"))
      (node (ref "L3") (pin "1") (pinfunction "1_1") (pintype "passive"))
    )
    (net (code "61") (name "Net-(LED1-DI)") (class "Default")
      (node (ref "DIN8") (pin "1") (pinfunction "1_1") (pintype "passive"))
      (node (ref "LED1") (pin "4-DIN") (pinfunction "DI_4-DIN") (pintype "input"))
    )
    (net (code "62") (name "Net-(LED8-DO)") (class "Default")
      (node (ref "JP2") (pin "1") (pinfunction "1_1") (pintype "passive"))
      (node (ref "LED8") (pin "2-DOUT") (pinfunction "DO_2-DOUT") (pintype "output"))
    )
    (net (code "63") (name "Net-(LED9-DI)") (class "Default")
      (node (ref "DIN7") (pin "1") (pinfunction "1_1") (pintype "passive"))
      (node (ref "LED9") (pin "4-DIN") (pinfunction "DI_4-DIN") (pintype "input"))
    )
    (net (code "64") (name "Net-(LED16-DO)") (class "Default")
      (node (ref "JP1") (pin "1") (pinfunction "1_1") (pintype "passive"))
      (node (ref "LED16") (pin "2-DOUT") (pinfunction "DO_2-DOUT") (pintype "output"))
    )
    (net (code "65") (name "Net-(LED17-DI)") (class "Default")
      (node (ref "DIN1") (pin "1") (pinfunction "1_1") (pintype "passive"))
      (node (ref "LED17") (pin "4-DIN") (pinfunction "DI_4-DIN") (pintype "input"))
    )
    (net (code "66") (name "Net-(LED24-DO)") (class "Default")
      (node (ref "JP3") (pin "1") (pinfunction "1_1") (pintype "passive"))
      (node (ref "LED24") (pin "2-DOUT") (pinfunction "DO_2-DOUT") (pintype "output"))
    )
    (net (code "67") (name "Net-(LED25-DI)") (class "Default")
      (node (ref "DIN2") (pin "1") (pinfunction "1_1") (pintype "passive"))
      (node (ref "LED25") (pin "4-DIN") (pinfunction "DI_4-DIN") (pintype "input"))
    )
    (net (code "68") (name "Net-(LED32-DO)") (class "Default")
      (node (ref "JP4") (pin "1") (pinfunction "1_1") (pintype "passive"))
      (node (ref "LED32") (pin "2-DOUT") (pinfunction "DO_2-DOUT") (pintype "output"))
    )
    (net (code "69") (name "Net-(LED33-DI)") (class "Default")
      (node (ref "DIN3") (pin "1") (pinfunction "1_1") (pintype "passive"))
      (node (ref "LED33") (pin "4-DIN") (pinfunction "DI_4-DIN") (pintype "input"))
    )
    (net (code "70") (name "Net-(LED40-DO)") (class "Default")
      (node (ref "JP5") (pin "1") (pinfunction "1_1") (pintype "passive"))
      (node (ref "LED40") (pin "2-DOUT") (pinfunction "DO_2-DOUT") (pintype "output"))
    )
    (net (code "71") (name "Net-(LED41-DI)") (class "Default")
      (node (ref "DIN4") (pin "1") (pinfunction "1_1") (pintype "passive"))
      (node (ref "LED41") (pin "4-DIN") (pinfunction "DI_4-DIN") (pintype "input"))
    )
    (net (code "72") (name "Net-(LED48-DO)") (class "Default")
      (node (ref "JP6") (pin "1") (pinfunction "1_1") (pintype "passive"))
      (node (ref "LED48") (pin "2-DOUT") (pinfunction "DO_2-DOUT") (pintype "output"))
    )
    (net (code "73") (name "Net-(LED49-DI)") (class "Default")
      (node (ref "DIN5") (pin "1") (pinfunction "1_1") (pintype "passive"))
      (node (ref "LED49") (pin "4-DIN") (pinfunction "DI_4-DIN") (pintype "input"))
    )
    (net (code "74") (name "Net-(LED56-DO)") (class "Default")
      (node (ref "JP7") (pin "1") (pinfunction "1_1") (pintype "passive"))
      (node (ref "LED56") (pin "2-DOUT") (pinfunction "DO_2-DOUT") (pintype "output"))
    )
    (net (code "75") (name "Net-(LED57-DI)") (class "Default")
      (node (ref "DIN6") (pin "1") (pinfunction "1_1") (pintype "passive"))
      (node (ref "LED57") (pin "4-DIN") (pinfunction "DI_4-DIN") (pintype "input"))
    )
    (net (code "76") (name "Net-(LED64-DO)") (class "Default")
      (node (ref "JP8") (pin "1") (pinfunction "1_1") (pintype "passive"))
      (node (ref "LED64") (pin "2-DOUT") (pinfunction "DO_2-DOUT") (pintype "output"))
    )
  )
)
